# 2_NAND-eMMC.net
KiCad netlist of a schematic drawn in Altium Designer
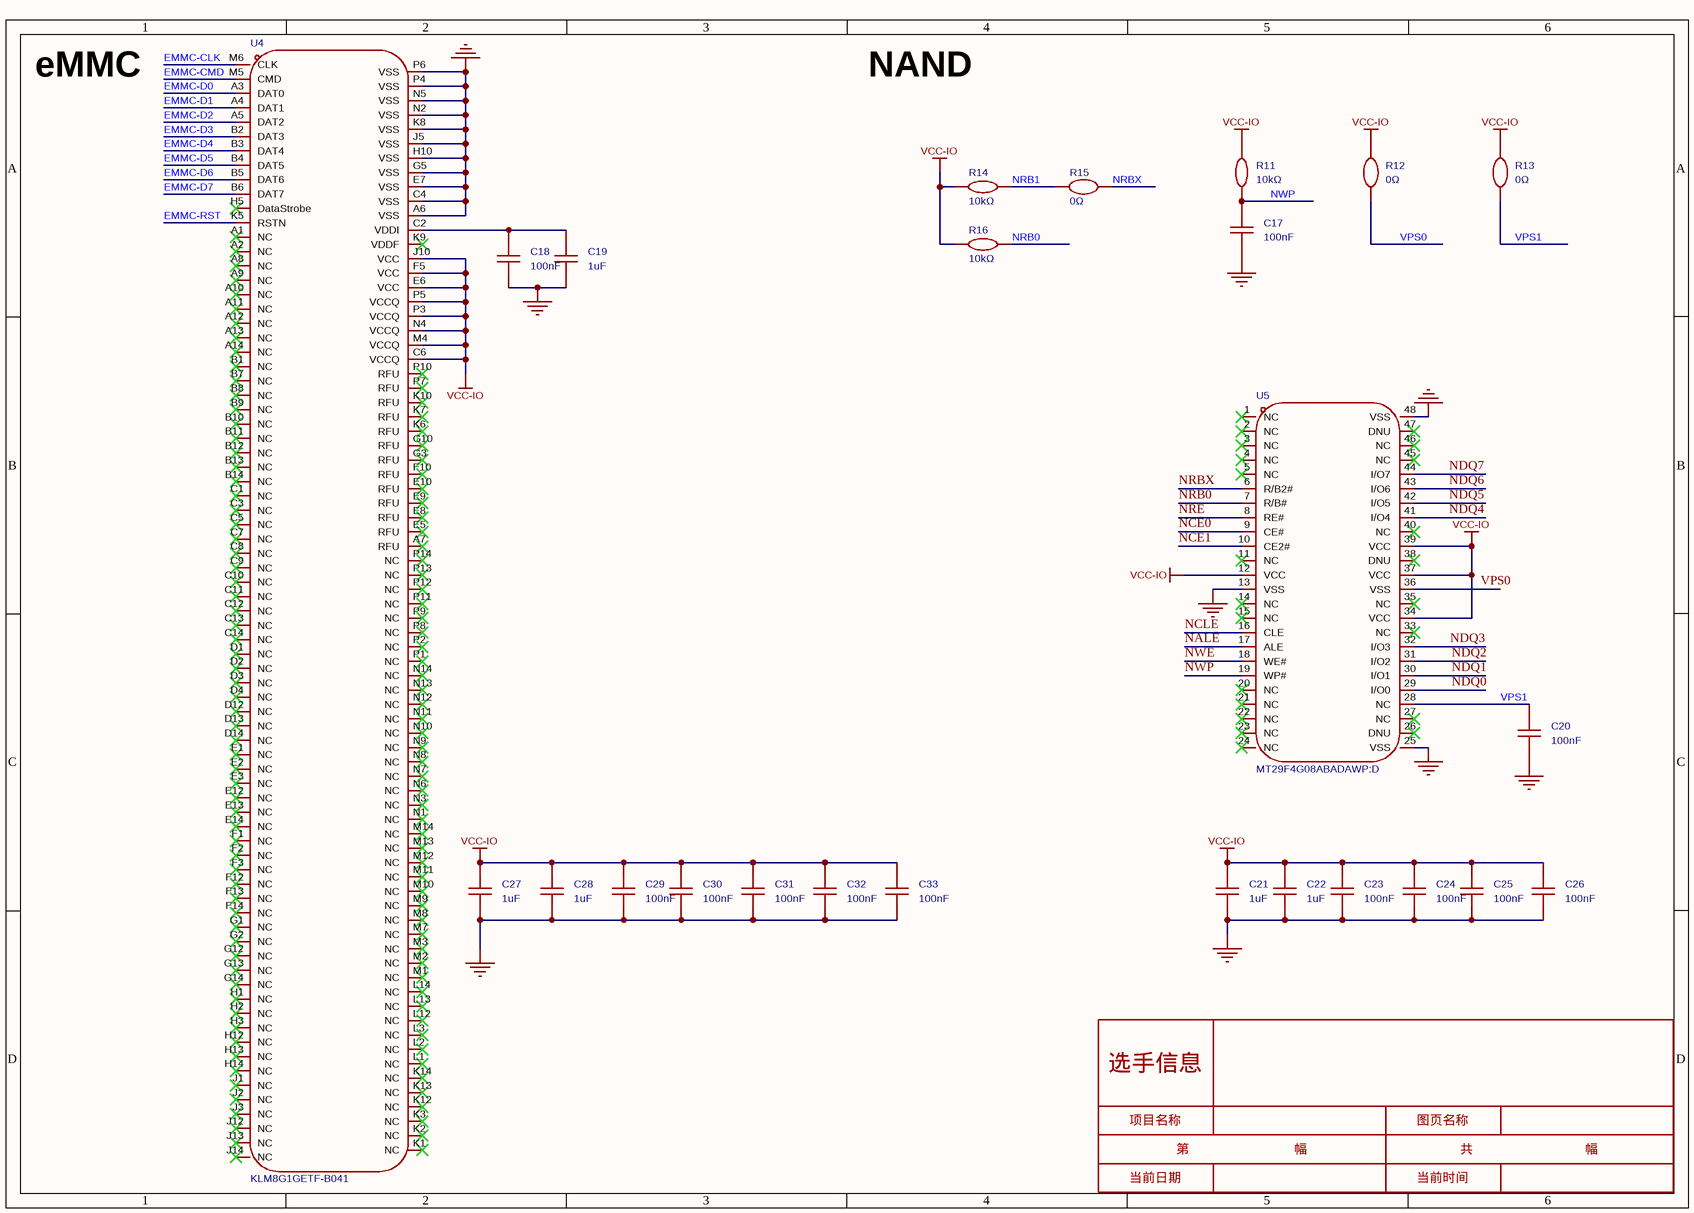
[diagram p0: 2_NAND-eMMC.schdoc]

(export (version "E")
  (design (tool "Eeschema 10.0.6"))
  (components
    (comp (ref "C17")
      (value "100nF")
      (footprint "C0402")
      (description "容值:100nF;精度:±10%;额定电压:16V;温度系数:X7R;")
      (fields (field (name "MANUFACTURER") "SAMSUNG(三星)") (field (name "MANUFACTURERPART") "CL05B104KO5NNNC"))
      (libsource (lib "altium-import") (part "root_3_CL05B104KO5NNNC_"))
    )
    (comp (ref "C18")
      (value "100nF")
      (footprint "C0402")
      (description "容值:100nF;精度:±10%;额定电压:16V;温度系数:X7R;")
      (fields (field (name "MANUFACTURER") "SAMSUNG(三星)") (field (name "MANUFACTURERPART") "CL05B104KO5NNNC"))
      (libsource (lib "altium-import") (part "root_3_CL05B104KO5NNNC_"))
    )
    (comp (ref "C19")
      (value "1uF")
      (footprint "C0402")
      (description "容值:1uF;精度:±10%;额定电压:50V;温度系数:X5R;")
      (fields (field (name "MANUFACTURER") "HRE(芯声)") (field (name "MANUFACTURERPART") "CGA0402X5R105K500GT"))
      (libsource (lib "altium-import") (part "root_3_CGA0402X5R105K500GT_"))
    )
    (comp (ref "C20")
      (value "100nF")
      (footprint "C0402")
      (description "容值:100nF;精度:±10%;额定电压:16V;温度系数:X7R;")
      (fields
        (field (name "MANUFACTURER") "SAMSUNG(三星)")
        (field (name "MANUFACTURER PART") "CL05B104KO5NNNC")
      )
      (libsource (lib "altium-import") (part "root_3_CL05B104KO5NNNC_"))
    )
    (comp (ref "C21")
      (value "1uF")
      (footprint "C0402")
      (description "容值:1uF;精度:±10%;额定电压:50V;温度系数:X5R;")
      (fields
        (field (name "MANUFACTURER") "HRE(芯声)")
        (field (name "MANUFACTURER PART") "CGA0402X5R105K500GT")
      )
      (libsource (lib "altium-import") (part "root_3_CGA0402X5R105K500GT_"))
    )
    (comp (ref "C22")
      (value "1uF")
      (footprint "C0402")
      (description "容值:1uF;精度:±10%;额定电压:50V;温度系数:X5R;")
      (fields
        (field (name "MANUFACTURER") "HRE(芯声)")
        (field (name "MANUFACTURER PART") "CGA0402X5R105K500GT")
      )
      (libsource (lib "altium-import") (part "root_3_CGA0402X5R105K500GT_"))
    )
    (comp (ref "C23")
      (value "100nF")
      (footprint "C0402")
      (description "容值:100nF;精度:±10%;额定电压:16V;温度系数:X7R;")
      (fields
        (field (name "MANUFACTURER") "SAMSUNG(三星)")
        (field (name "MANUFACTURER PART") "CL05B104KO5NNNC")
      )
      (libsource (lib "altium-import") (part "root_3_CL05B104KO5NNNC_"))
    )
    (comp (ref "C24")
      (value "100nF")
      (footprint "C0402")
      (description "容值:100nF;精度:±10%;额定电压:16V;温度系数:X7R;")
      (fields
        (field (name "MANUFACTURER") "SAMSUNG(三星)")
        (field (name "MANUFACTURER PART") "CL05B104KO5NNNC")
      )
      (libsource (lib "altium-import") (part "root_3_CL05B104KO5NNNC_"))
    )
    (comp (ref "C25")
      (value "100nF")
      (footprint "C0402")
      (description "容值:100nF;精度:±10%;额定电压:16V;温度系数:X7R;")
      (fields
        (field (name "MANUFACTURER") "SAMSUNG(三星)")
        (field (name "MANUFACTURER PART") "CL05B104KO5NNNC")
      )
      (libsource (lib "altium-import") (part "root_3_CL05B104KO5NNNC_"))
    )
    (comp (ref "C26")
      (value "100nF")
      (footprint "C0402")
      (description "容值:100nF;精度:±10%;额定电压:16V;温度系数:X7R;")
      (fields
        (field (name "MANUFACTURER") "SAMSUNG(三星)")
        (field (name "MANUFACTURER PART") "CL05B104KO5NNNC")
      )
      (libsource (lib "altium-import") (part "root_3_CL05B104KO5NNNC_"))
    )
    (comp (ref "C27")
      (value "1uF")
      (footprint "C0402")
      (description "容值:1uF;精度:±10%;额定电压:50V;温度系数:X5R;")
      (fields (field (name "MANUFACTURER") "HRE(芯声)") (field (name "MANUFACTURERPART") "CGA0402X5R105K500GT"))
      (libsource (lib "altium-import") (part "root_3_CGA0402X5R105K500GT_"))
    )
    (comp (ref "C28")
      (value "1uF")
      (footprint "C0402")
      (description "容值:1uF;精度:±10%;额定电压:50V;温度系数:X5R;")
      (fields (field (name "MANUFACTURER") "HRE(芯声)") (field (name "MANUFACTURERPART") "CGA0402X5R105K500GT"))
      (libsource (lib "altium-import") (part "root_3_CGA0402X5R105K500GT_"))
    )
    (comp (ref "C29")
      (value "100nF")
      (footprint "C0402")
      (description "容值:100nF;精度:±10%;额定电压:16V;温度系数:X7R;")
      (fields (field (name "MANUFACTURER") "SAMSUNG(三星)") (field (name "MANUFACTURERPART") "CL05B104KO5NNNC"))
      (libsource (lib "altium-import") (part "root_3_CL05B104KO5NNNC_"))
    )
    (comp (ref "C30")
      (value "100nF")
      (footprint "C0402")
      (description "容值:100nF;精度:±10%;额定电压:16V;温度系数:X7R;")
      (fields
        (field (name "MANUFACTURER") "SAMSUNG(三星)")
        (field (name "MANUFACTURER PART") "CL05B104KO5NNNC")
      )
      (libsource (lib "altium-import") (part "root_3_CL05B104KO5NNNC_"))
    )
    (comp (ref "C31")
      (value "100nF")
      (footprint "C0402")
      (description "容值:100nF;精度:±10%;额定电压:16V;温度系数:X7R;")
      (fields
        (field (name "MANUFACTURER") "SAMSUNG(三星)")
        (field (name "MANUFACTURER PART") "CL05B104KO5NNNC")
      )
      (libsource (lib "altium-import") (part "root_3_CL05B104KO5NNNC_"))
    )
    (comp (ref "C32")
      (value "100nF")
      (footprint "C0402")
      (description "容值:100nF;精度:±10%;额定电压:16V;温度系数:X7R;")
      (fields
        (field (name "MANUFACTURER") "SAMSUNG(三星)")
        (field (name "MANUFACTURER PART") "CL05B104KO5NNNC")
      )
      (libsource (lib "altium-import") (part "root_3_CL05B104KO5NNNC_"))
    )
    (comp (ref "C33")
      (value "100nF")
      (footprint "C0402")
      (description "容值:100nF;精度:±10%;额定电压:16V;温度系数:X7R;")
      (fields
        (field (name "MANUFACTURER") "SAMSUNG(三星)")
        (field (name "MANUFACTURER PART") "CL05B104KO5NNNC")
      )
      (libsource (lib "altium-import") (part "root_3_CL05B104KO5NNNC_"))
    )
    (comp (ref "R11")
      (value "10kΩ")
      (footprint "R0402")
      (description "电阻类型:厚膜电阻;阻值:10kΩ;精度:±1%;功率:62.5mW;工作电压:50V;温度系数:±100ppm/℃;")
      (fields (field (name "MANUFACTURER") "YAGEO(国巨)") (field (name "MANUFACTURERPART") "RC0402FR-0710KL"))
      (libsource (lib "altium-import") (part "root_1_RC0402FR-0710KL_"))
    )
    (comp (ref "R12")
      (value "0Ω")
      (footprint "R0402")
      (description "电阻类型:厚膜电阻;阻值:0Ω;精度:±5%;功率:62.5mW;工作电压:50V;")
      (fields (field (name "MANUFACTURER") "FOJAN(富捷)") (field (name "MANUFACTURERPART") "FRC0402P000 TS"))
      (libsource (lib "altium-import") (part "root_1_FRC0402P000 TS_"))
    )
    (comp (ref "R13")
      (value "0Ω")
      (footprint "R0402")
      (description "电阻类型:厚膜电阻;阻值:0Ω;精度:±5%;功率:62.5mW;工作电压:50V;")
      (fields (field (name "MANUFACTURER") "FOJAN(富捷)") (field (name "MANUFACTURERPART") "FRC0402P000 TS"))
      (libsource (lib "altium-import") (part "root_1_FRC0402P000 TS_"))
    )
    (comp (ref "R14")
      (value "10kΩ")
      (footprint "R0402")
      (description "电阻类型:厚膜电阻;阻值:10kΩ;精度:±1%;功率:62.5mW;工作电压:50V;温度系数:±100ppm/℃;")
      (fields (field (name "MANUFACTURER") "YAGEO(国巨)") (field (name "MANUFACTURERPART") "RC0402FR-0710KL"))
      (libsource (lib "altium-import") (part "root_2_RC0402FR-0710KL_"))
    )
    (comp (ref "R15")
      (value "0Ω")
      (footprint "R0402")
      (description "电阻类型:厚膜电阻;阻值:0Ω;精度:±5%;功率:62.5mW;工作电压:50V;")
      (fields (field (name "MANUFACTURER") "FOJAN(富捷)") (field (name "MANUFACTURERPART") "FRC0402P000 TS"))
      (libsource (lib "altium-import") (part "root_2_FRC0402P000 TS_"))
    )
    (comp (ref "R16")
      (value "10kΩ")
      (footprint "R0402")
      (description "电阻类型:厚膜电阻;阻值:10kΩ;精度:±1%;功率:62.5mW;工作电压:50V;温度系数:±100ppm/℃;")
      (fields (field (name "MANUFACTURER") "YAGEO(国巨)") (field (name "MANUFACTURERPART") "RC0402FR-0710KL"))
      (libsource (lib "altium-import") (part "root_2_RC0402FR-0710KL_"))
    )
    (comp (ref "U4")
      (value "KLM8G1GETF-B041")
      (footprint "FBGA-153_L13.0-W11.5-P0.50_KLMAG1JETD-B041")
      (description "配置:-;接口类型:eMMC 5.1;存储容量:8GB;")
      (fields (field (name "MANUFACTURER") "SAMSUNG(三星半导体)"))
      (libsource (lib "altium-import") (part "root_0_KLM8G1GETF-B041_"))
    )
    (comp (ref "U5")
      (value "MT29F4G08ABADAWP:D")
      (footprint "TSOP-48_L18.5-W12.2-P0.50-LS20.0-TL")
      (description "存储容量:4Gbit;时钟频率(fc):-;工作电压:2.7V~3.6V;")
      (fields (field (name "MANUFACTURER") "micron(镁光)"))
      (libsource (lib "altium-import") (part "root_0_MT29F4G08ABADAWP{colon}D_"))
    )
  )
  (nets
    (net (code "2") (name "/EMMC-CLK") (class "Default")
      (node (ref "U4") (pin "M6") (pinfunction "CLK_M6") (pintype "passive"))
    )
    (net (code "3") (name "/EMMC-CMD") (class "Default")
      (node (ref "U4") (pin "M5") (pinfunction "CMD_M5") (pintype "passive"))
    )
    (net (code "4") (name "/EMMC-D0") (class "Default")
      (node (ref "U4") (pin "A3") (pinfunction "DAT0_A3") (pintype "passive"))
    )
    (net (code "5") (name "/EMMC-D1") (class "Default")
      (node (ref "U4") (pin "A4") (pinfunction "DAT1_A4") (pintype "passive"))
    )
    (net (code "6") (name "/EMMC-D2") (class "Default")
      (node (ref "U4") (pin "A5") (pinfunction "DAT2_A5") (pintype "passive"))
    )
    (net (code "7") (name "/EMMC-D3") (class "Default")
      (node (ref "U4") (pin "B2") (pinfunction "DAT3_B2") (pintype "passive"))
    )
    (net (code "8") (name "/EMMC-D4") (class "Default")
      (node (ref "U4") (pin "B3") (pinfunction "DAT4_B3") (pintype "passive"))
    )
    (net (code "9") (name "/EMMC-D5") (class "Default")
      (node (ref "U4") (pin "B4") (pinfunction "DAT5_B4") (pintype "passive"))
    )
    (net (code "10") (name "/EMMC-D6") (class "Default")
      (node (ref "U4") (pin "B5") (pinfunction "DAT6_B5") (pintype "passive"))
    )
    (net (code "11") (name "/EMMC-D7") (class "Default")
      (node (ref "U4") (pin "B6") (pinfunction "DAT7_B6") (pintype "passive"))
    )
    (net (code "12") (name "/EMMC-RST") (class "Default")
      (node (ref "U4") (pin "K5") (pinfunction "RSTN_K5") (pintype "passive"))
    )
    (net (code "13") (name "/NALE") (class "Default")
      (node (ref "U5") (pin "17") (pinfunction "ALE_17") (pintype "passive"))
    )
    (net (code "14") (name "/NCE0") (class "Default")
      (node (ref "U5") (pin "9") (pinfunction "CE#_9") (pintype "passive"))
    )
    (net (code "15") (name "/NCE1") (class "Default")
      (node (ref "U5") (pin "10") (pinfunction "CE2#_10") (pintype "passive"))
    )
    (net (code "16") (name "/NCLE") (class "Default")
      (node (ref "U5") (pin "16") (pinfunction "CLE_16") (pintype "passive"))
    )
    (net (code "17") (name "/NDQ0") (class "Default")
      (node (ref "U5") (pin "29") (pinfunction "I/O0_29") (pintype "passive"))
    )
    (net (code "18") (name "/NDQ1") (class "Default")
      (node (ref "U5") (pin "30") (pinfunction "I/O1_30") (pintype "passive"))
    )
    (net (code "19") (name "/NDQ2") (class "Default")
      (node (ref "U5") (pin "31") (pinfunction "I/O2_31") (pintype "passive"))
    )
    (net (code "20") (name "/NDQ3") (class "Default")
      (node (ref "U5") (pin "32") (pinfunction "I/O3_32") (pintype "passive"))
    )
    (net (code "21") (name "/NDQ4") (class "Default")
      (node (ref "U5") (pin "41") (pinfunction "I/O4_41") (pintype "passive"))
    )
    (net (code "22") (name "/NDQ5") (class "Default")
      (node (ref "U5") (pin "42") (pinfunction "I/O5_42") (pintype "passive"))
    )
    (net (code "23") (name "/NDQ6") (class "Default")
      (node (ref "U5") (pin "43") (pinfunction "I/O6_43") (pintype "passive"))
    )
    (net (code "24") (name "/NDQ7") (class "Default")
      (node (ref "U5") (pin "44") (pinfunction "I/O7_44") (pintype "passive"))
    )
    (net (code "25") (name "/NRB0") (class "Default")
      (node (ref "R16") (pin "1") (pinfunction "1_1") (pintype "passive"))
      (node (ref "U5") (pin "7") (pinfunction "R/B#_7") (pintype "passive"))
    )
    (net (code "26") (name "/NRB1") (class "Default")
      (node (ref "R14") (pin "1") (pinfunction "1_1") (pintype "passive"))
      (node (ref "R15") (pin "2") (pinfunction "2_2") (pintype "passive"))
    )
    (net (code "27") (name "/NRBX") (class "Default")
      (node (ref "R15") (pin "1") (pinfunction "1_1") (pintype "passive"))
      (node (ref "U5") (pin "6") (pinfunction "R/B2#_6") (pintype "passive"))
    )
    (net (code "28") (name "/NRE") (class "Default")
      (node (ref "U5") (pin "8") (pinfunction "RE#_8") (pintype "passive"))
    )
    (net (code "29") (name "/NWE") (class "Default")
      (node (ref "U5") (pin "18") (pinfunction "WE#_18") (pintype "passive"))
    )
    (net (code "30") (name "/NWP") (class "Default")
      (node (ref "C17") (pin "1") (pinfunction "1_1") (pintype "passive"))
      (node (ref "R11") (pin "1") (pinfunction "1_1") (pintype "passive"))
      (node (ref "U5") (pin "19") (pinfunction "WP#_19") (pintype "passive"))
    )
    (net (code "31") (name "/VPS0") (class "Default")
      (node (ref "R12") (pin "1") (pinfunction "1_1") (pintype "passive"))
      (node (ref "U5") (pin "36") (pinfunction "VSS_36") (pintype "passive"))
    )
    (net (code "32") (name "/VPS1") (class "Default")
      (node (ref "C20") (pin "1") (pinfunction "1_1") (pintype "passive"))
      (node (ref "R13") (pin "1") (pinfunction "1_1") (pintype "passive"))
      (node (ref "U5") (pin "28") (pinfunction "NC_28") (pintype "passive"))
    )
    (net (code "33") (name "GND") (class "Default")
      (node (ref "C17") (pin "2") (pinfunction "2_2") (pintype "passive"))
      (node (ref "C18") (pin "2") (pinfunction "2_2") (pintype "passive"))
      (node (ref "C19") (pin "2") (pinfunction "2_2") (pintype "passive"))
      (node (ref "C20") (pin "2") (pinfunction "2_2") (pintype "passive"))
      (node (ref "C21") (pin "2") (pinfunction "2_2") (pintype "passive"))
      (node (ref "C22") (pin "2") (pinfunction "2_2") (pintype "passive"))
      (node (ref "C23") (pin "2") (pinfunction "2_2") (pintype "passive"))
      (node (ref "C24") (pin "2") (pinfunction "2_2") (pintype "passive"))
      (node (ref "C25") (pin "2") (pinfunction "2_2") (pintype "passive"))
      (node (ref "C26") (pin "2") (pinfunction "2_2") (pintype "passive"))
      (node (ref "C27") (pin "2") (pinfunction "2_2") (pintype "passive"))
      (node (ref "C28") (pin "2") (pinfunction "2_2") (pintype "passive"))
      (node (ref "C29") (pin "2") (pinfunction "2_2") (pintype "passive"))
      (node (ref "C30") (pin "2") (pinfunction "2_2") (pintype "passive"))
      (node (ref "C31") (pin "2") (pinfunction "2_2") (pintype "passive"))
      (node (ref "C32") (pin "2") (pinfunction "2_2") (pintype "passive"))
      (node (ref "C33") (pin "2") (pinfunction "2_2") (pintype "passive"))
      (node (ref "U4") (pin "A6") (pinfunction "VSS_A6") (pintype "passive"))
      (node (ref "U4") (pin "C4") (pinfunction "VSS_C4") (pintype "passive"))
      (node (ref "U4") (pin "E7") (pinfunction "VSS_E7") (pintype "passive"))
      (node (ref "U4") (pin "G5") (pinfunction "VSS_G5") (pintype "passive"))
      (node (ref "U4") (pin "H10") (pinfunction "VSS_H10") (pintype "passive"))
      (node (ref "U4") (pin "J5") (pinfunction "VSS_J5") (pintype "passive"))
      (node (ref "U4") (pin "K8") (pinfunction "VSS_K8") (pintype "passive"))
      (node (ref "U4") (pin "N2") (pinfunction "VSS_N2") (pintype "passive"))
      (node (ref "U4") (pin "N5") (pinfunction "VSS_N5") (pintype "passive"))
      (node (ref "U4") (pin "P4") (pinfunction "VSS_P4") (pintype "passive"))
      (node (ref "U4") (pin "P6") (pinfunction "VSS_P6") (pintype "passive"))
      (node (ref "U5") (pin "13") (pinfunction "VSS_13") (pintype "passive"))
      (node (ref "U5") (pin "25") (pinfunction "VSS_25") (pintype "passive"))
      (node (ref "U5") (pin "48") (pinfunction "VSS_48") (pintype "passive"))
    )
    (net (code "34") (name "Net-(U4-VDDI)") (class "Default")
      (node (ref "C18") (pin "1") (pinfunction "1_1") (pintype "passive"))
      (node (ref "C19") (pin "1") (pinfunction "1_1") (pintype "passive"))
      (node (ref "U4") (pin "C2") (pinfunction "VDDI_C2") (pintype "passive"))
    )
    (net (code "35") (name "VCC-IO") (class "Default")
      (node (ref "C21") (pin "1") (pinfunction "1_1") (pintype "passive"))
      (node (ref "C22") (pin "1") (pinfunction "1_1") (pintype "passive"))
      (node (ref "C23") (pin "1") (pinfunction "1_1") (pintype "passive"))
      (node (ref "C24") (pin "1") (pinfunction "1_1") (pintype "passive"))
      (node (ref "C25") (pin "1") (pinfunction "1_1") (pintype "passive"))
      (node (ref "C26") (pin "1") (pinfunction "1_1") (pintype "passive"))
      (node (ref "C27") (pin "1") (pinfunction "1_1") (pintype "passive"))
      (node (ref "C28") (pin "1") (pinfunction "1_1") (pintype "passive"))
      (node (ref "C29") (pin "1") (pinfunction "1_1") (pintype "passive"))
      (node (ref "C30") (pin "1") (pinfunction "1_1") (pintype "passive"))
      (node (ref "C31") (pin "1") (pinfunction "1_1") (pintype "passive"))
      (node (ref "C32") (pin "1") (pinfunction "1_1") (pintype "passive"))
      (node (ref "C33") (pin "1") (pinfunction "1_1") (pintype "passive"))
      (node (ref "R11") (pin "2") (pinfunction "2_2") (pintype "passive"))
      (node (ref "R12") (pin "2") (pinfunction "2_2") (pintype "passive"))
      (node (ref "R13") (pin "2") (pinfunction "2_2") (pintype "passive"))
      (node (ref "R14") (pin "2") (pinfunction "2_2") (pintype "passive"))
      (node (ref "R16") (pin "2") (pinfunction "2_2") (pintype "passive"))
      (node (ref "U4") (pin "C6") (pinfunction "VCCQ_C6") (pintype "passive"))
      (node (ref "U4") (pin "E6") (pinfunction "VCC_E6") (pintype "passive"))
      (node (ref "U4") (pin "F5") (pinfunction "VCC_F5") (pintype "passive"))
      (node (ref "U4") (pin "J10") (pinfunction "VCC_J10") (pintype "passive"))
      (node (ref "U4") (pin "M4") (pinfunction "VCCQ_M4") (pintype "passive"))
      (node (ref "U4") (pin "N4") (pinfunction "VCCQ_N4") (pintype "passive"))
      (node (ref "U4") (pin "P3") (pinfunction "VCCQ_P3") (pintype "passive"))
      (node (ref "U4") (pin "P5") (pinfunction "VCCQ_P5") (pintype "passive"))
      (node (ref "U5") (pin "12") (pinfunction "VCC_12") (pintype "passive"))
      (node (ref "U5") (pin "34") (pinfunction "VCC_34") (pintype "passive"))
      (node (ref "U5") (pin "37") (pinfunction "VCC_37") (pintype "passive"))
      (node (ref "U5") (pin "39") (pinfunction "VCC_39") (pintype "passive"))
    )
    (net (code "36") (name "unconnected-(U4-DataStrobe-PadH5)") (class "Default")
      (node (ref "U4") (pin "H5") (pinfunction "DataStrobe_H5") (pintype "passive+no_connect"))
    )
    (net (code "37") (name "unconnected-(U4-NC-PadA1)") (class "Default")
      (node (ref "U4") (pin "A1") (pinfunction "NC_A1") (pintype "passive+no_connect"))
    )
    (net (code "38") (name "unconnected-(U4-NC-PadA2)") (class "Default")
      (node (ref "U4") (pin "A2") (pinfunction "NC_A2") (pintype "passive+no_connect"))
    )
    (net (code "39") (name "unconnected-(U4-NC-PadA8)") (class "Default")
      (node (ref "U4") (pin "A8") (pinfunction "NC_A8") (pintype "passive+no_connect"))
    )
    (net (code "40") (name "unconnected-(U4-NC-PadA9)") (class "Default")
      (node (ref "U4") (pin "A9") (pinfunction "NC_A9") (pintype "passive+no_connect"))
    )
    (net (code "41") (name "unconnected-(U4-NC-PadA10)") (class "Default")
      (node (ref "U4") (pin "A10") (pinfunction "NC_A10") (pintype "passive+no_connect"))
    )
    (net (code "42") (name "unconnected-(U4-NC-PadA11)") (class "Default")
      (node (ref "U4") (pin "A11") (pinfunction "NC_A11") (pintype "passive+no_connect"))
    )
    (net (code "43") (name "unconnected-(U4-NC-PadA12)") (class "Default")
      (node (ref "U4") (pin "A12") (pinfunction "NC_A12") (pintype "passive+no_connect"))
    )
    (net (code "44") (name "unconnected-(U4-NC-PadA13)") (class "Default")
      (node (ref "U4") (pin "A13") (pinfunction "NC_A13") (pintype "passive+no_connect"))
    )
    (net (code "45") (name "unconnected-(U4-NC-PadA14)") (class "Default")
      (node (ref "U4") (pin "A14") (pinfunction "NC_A14") (pintype "passive+no_connect"))
    )
    (net (code "46") (name "unconnected-(U4-NC-PadB1)") (class "Default")
      (node (ref "U4") (pin "B1") (pinfunction "NC_B1") (pintype "passive+no_connect"))
    )
    (net (code "47") (name "unconnected-(U4-NC-PadB7)") (class "Default")
      (node (ref "U4") (pin "B7") (pinfunction "NC_B7") (pintype "passive+no_connect"))
    )
    (net (code "48") (name "unconnected-(U4-NC-PadB8)") (class "Default")
      (node (ref "U4") (pin "B8") (pinfunction "NC_B8") (pintype "passive+no_connect"))
    )
    (net (code "49") (name "unconnected-(U4-NC-PadB9)") (class "Default")
      (node (ref "U4") (pin "B9") (pinfunction "NC_B9") (pintype "passive+no_connect"))
    )
    (net (code "50") (name "unconnected-(U4-NC-PadB10)") (class "Default")
      (node (ref "U4") (pin "B10") (pinfunction "NC_B10") (pintype "passive+no_connect"))
    )
    (net (code "51") (name "unconnected-(U4-NC-PadB11)") (class "Default")
      (node (ref "U4") (pin "B11") (pinfunction "NC_B11") (pintype "passive+no_connect"))
    )
    (net (code "52") (name "unconnected-(U4-NC-PadB12)") (class "Default")
      (node (ref "U4") (pin "B12") (pinfunction "NC_B12") (pintype "passive+no_connect"))
    )
    (net (code "53") (name "unconnected-(U4-NC-PadB13)") (class "Default")
      (node (ref "U4") (pin "B13") (pinfunction "NC_B13") (pintype "passive+no_connect"))
    )
    (net (code "54") (name "unconnected-(U4-NC-PadB14)") (class "Default")
      (node (ref "U4") (pin "B14") (pinfunction "NC_B14") (pintype "passive+no_connect"))
    )
    (net (code "55") (name "unconnected-(U4-NC-PadC1)") (class "Default")
      (node (ref "U4") (pin "C1") (pinfunction "NC_C1") (pintype "passive+no_connect"))
    )
    (net (code "56") (name "unconnected-(U4-NC-PadC3)") (class "Default")
      (node (ref "U4") (pin "C3") (pinfunction "NC_C3") (pintype "passive+no_connect"))
    )
    (net (code "57") (name "unconnected-(U4-NC-PadC5)") (class "Default")
      (node (ref "U4") (pin "C5") (pinfunction "NC_C5") (pintype "passive+no_connect"))
    )
    (net (code "58") (name "unconnected-(U4-NC-PadC7)") (class "Default")
      (node (ref "U4") (pin "C7") (pinfunction "NC_C7") (pintype "passive+no_connect"))
    )
    (net (code "59") (name "unconnected-(U4-NC-PadC8)") (class "Default")
      (node (ref "U4") (pin "C8") (pinfunction "NC_C8") (pintype "passive+no_connect"))
    )
    (net (code "60") (name "unconnected-(U4-NC-PadC9)") (class "Default")
      (node (ref "U4") (pin "C9") (pinfunction "NC_C9") (pintype "passive+no_connect"))
    )
    (net (code "61") (name "unconnected-(U4-NC-PadC10)") (class "Default")
      (node (ref "U4") (pin "C10") (pinfunction "NC_C10") (pintype "passive+no_connect"))
    )
    (net (code "62") (name "unconnected-(U4-NC-PadC11)") (class "Default")
      (node (ref "U4") (pin "C11") (pinfunction "NC_C11") (pintype "passive+no_connect"))
    )
    (net (code "63") (name "unconnected-(U4-NC-PadC12)") (class "Default")
      (node (ref "U4") (pin "C12") (pinfunction "NC_C12") (pintype "passive+no_connect"))
    )
    (net (code "64") (name "unconnected-(U4-NC-PadC13)") (class "Default")
      (node (ref "U4") (pin "C13") (pinfunction "NC_C13") (pintype "passive+no_connect"))
    )
    (net (code "65") (name "unconnected-(U4-NC-PadC14)") (class "Default")
      (node (ref "U4") (pin "C14") (pinfunction "NC_C14") (pintype "passive+no_connect"))
    )
    (net (code "66") (name "unconnected-(U4-NC-PadD1)") (class "Default")
      (node (ref "U4") (pin "D1") (pinfunction "NC_D1") (pintype "passive+no_connect"))
    )
    (net (code "67") (name "unconnected-(U4-NC-PadD2)") (class "Default")
      (node (ref "U4") (pin "D2") (pinfunction "NC_D2") (pintype "passive+no_connect"))
    )
    (net (code "68") (name "unconnected-(U4-NC-PadD3)") (class "Default")
      (node (ref "U4") (pin "D3") (pinfunction "NC_D3") (pintype "passive+no_connect"))
    )
    (net (code "69") (name "unconnected-(U4-NC-PadD4)") (class "Default")
      (node (ref "U4") (pin "D4") (pinfunction "NC_D4") (pintype "passive+no_connect"))
    )
    (net (code "70") (name "unconnected-(U4-NC-PadD12)") (class "Default")
      (node (ref "U4") (pin "D12") (pinfunction "NC_D12") (pintype "passive+no_connect"))
    )
    (net (code "71") (name "unconnected-(U4-NC-PadD13)") (class "Default")
      (node (ref "U4") (pin "D13") (pinfunction "NC_D13") (pintype "passive+no_connect"))
    )
    (net (code "72") (name "unconnected-(U4-NC-PadD14)") (class "Default")
      (node (ref "U4") (pin "D14") (pinfunction "NC_D14") (pintype "passive+no_connect"))
    )
    (net (code "73") (name "unconnected-(U4-NC-PadE1)") (class "Default")
      (node (ref "U4") (pin "E1") (pinfunction "NC_E1") (pintype "passive+no_connect"))
    )
    (net (code "74") (name "unconnected-(U4-NC-PadE2)") (class "Default")
      (node (ref "U4") (pin "E2") (pinfunction "NC_E2") (pintype "passive+no_connect"))
    )
    (net (code "75") (name "unconnected-(U4-NC-PadE3)") (class "Default")
      (node (ref "U4") (pin "E3") (pinfunction "NC_E3") (pintype "passive+no_connect"))
    )
    (net (code "76") (name "unconnected-(U4-NC-PadE12)") (class "Default")
      (node (ref "U4") (pin "E12") (pinfunction "NC_E12") (pintype "passive+no_connect"))
    )
    (net (code "77") (name "unconnected-(U4-NC-PadE13)") (class "Default")
      (node (ref "U4") (pin "E13") (pinfunction "NC_E13") (pintype "passive+no_connect"))
    )
    (net (code "78") (name "unconnected-(U4-NC-PadE14)") (class "Default")
      (node (ref "U4") (pin "E14") (pinfunction "NC_E14") (pintype "passive+no_connect"))
    )
    (net (code "79") (name "unconnected-(U4-NC-PadF1)") (class "Default")
      (node (ref "U4") (pin "F1") (pinfunction "NC_F1") (pintype "passive+no_connect"))
    )
    (net (code "80") (name "unconnected-(U4-NC-PadF2)") (class "Default")
      (node (ref "U4") (pin "F2") (pinfunction "NC_F2") (pintype "passive+no_connect"))
    )
    (net (code "81") (name "unconnected-(U4-NC-PadF3)") (class "Default")
      (node (ref "U4") (pin "F3") (pinfunction "NC_F3") (pintype "passive+no_connect"))
    )
    (net (code "82") (name "unconnected-(U4-NC-PadF12)") (class "Default")
      (node (ref "U4") (pin "F12") (pinfunction "NC_F12") (pintype "passive+no_connect"))
    )
    (net (code "83") (name "unconnected-(U4-NC-PadF13)") (class "Default")
      (node (ref "U4") (pin "F13") (pinfunction "NC_F13") (pintype "passive+no_connect"))
    )
    (net (code "84") (name "unconnected-(U4-NC-PadF14)") (class "Default")
      (node (ref "U4") (pin "F14") (pinfunction "NC_F14") (pintype "passive+no_connect"))
    )
    (net (code "85") (name "unconnected-(U4-NC-PadG1)") (class "Default")
      (node (ref "U4") (pin "G1") (pinfunction "NC_G1") (pintype "passive+no_connect"))
    )
    (net (code "86") (name "unconnected-(U4-NC-PadG2)") (class "Default")
      (node (ref "U4") (pin "G2") (pinfunction "NC_G2") (pintype "passive+no_connect"))
    )
    (net (code "87") (name "unconnected-(U4-NC-PadG12)") (class "Default")
      (node (ref "U4") (pin "G12") (pinfunction "NC_G12") (pintype "passive+no_connect"))
    )
    (net (code "88") (name "unconnected-(U4-NC-PadG13)") (class "Default")
      (node (ref "U4") (pin "G13") (pinfunction "NC_G13") (pintype "passive+no_connect"))
    )
    (net (code "89") (name "unconnected-(U4-NC-PadG14)") (class "Default")
      (node (ref "U4") (pin "G14") (pinfunction "NC_G14") (pintype "passive+no_connect"))
    )
    (net (code "90") (name "unconnected-(U4-NC-PadH1)") (class "Default")
      (node (ref "U4") (pin "H1") (pinfunction "NC_H1") (pintype "passive+no_connect"))
    )
    (net (code "91") (name "unconnected-(U4-NC-PadH2)") (class "Default")
      (node (ref "U4") (pin "H2") (pinfunction "NC_H2") (pintype "passive+no_connect"))
    )
    (net (code "92") (name "unconnected-(U4-NC-PadH3)") (class "Default")
      (node (ref "U4") (pin "H3") (pinfunction "NC_H3") (pintype "passive+no_connect"))
    )
    (net (code "93") (name "unconnected-(U4-NC-PadH12)") (class "Default")
      (node (ref "U4") (pin "H12") (pinfunction "NC_H12") (pintype "passive+no_connect"))
    )
    (net (code "94") (name "unconnected-(U4-NC-PadH13)") (class "Default")
      (node (ref "U4") (pin "H13") (pinfunction "NC_H13") (pintype "passive+no_connect"))
    )
    (net (code "95") (name "unconnected-(U4-NC-PadH14)") (class "Default")
      (node (ref "U4") (pin "H14") (pinfunction "NC_H14") (pintype "passive+no_connect"))
    )
    (net (code "96") (name "unconnected-(U4-NC-PadJ1)") (class "Default")
      (node (ref "U4") (pin "J1") (pinfunction "NC_J1") (pintype "passive+no_connect"))
    )
    (net (code "97") (name "unconnected-(U4-NC-PadJ2)") (class "Default")
      (node (ref "U4") (pin "J2") (pinfunction "NC_J2") (pintype "passive+no_connect"))
    )
    (net (code "98") (name "unconnected-(U4-NC-PadJ3)") (class "Default")
      (node (ref "U4") (pin "J3") (pinfunction "NC_J3") (pintype "passive+no_connect"))
    )
    (net (code "99") (name "unconnected-(U4-NC-PadJ12)") (class "Default")
      (node (ref "U4") (pin "J12") (pinfunction "NC_J12") (pintype "passive+no_connect"))
    )
    (net (code "100") (name "unconnected-(U4-NC-PadJ13)") (class "Default")
      (node (ref "U4") (pin "J13") (pinfunction "NC_J13") (pintype "passive+no_connect"))
    )
    (net (code "101") (name "unconnected-(U4-NC-PadJ14)") (class "Default")
      (node (ref "U4") (pin "J14") (pinfunction "NC_J14") (pintype "passive+no_connect"))
    )
    (net (code "102") (name "unconnected-(U4-NC-PadK1)") (class "Default")
      (node (ref "U4") (pin "K1") (pinfunction "NC_K1") (pintype "passive+no_connect"))
    )
    (net (code "103") (name "unconnected-(U4-NC-PadK2)") (class "Default")
      (node (ref "U4") (pin "K2") (pinfunction "NC_K2") (pintype "passive+no_connect"))
    )
    (net (code "104") (name "unconnected-(U4-NC-PadK3)") (class "Default")
      (node (ref "U4") (pin "K3") (pinfunction "NC_K3") (pintype "passive+no_connect"))
    )
    (net (code "105") (name "unconnected-(U4-NC-PadK12)") (class "Default")
      (node (ref "U4") (pin "K12") (pinfunction "NC_K12") (pintype "passive+no_connect"))
    )
    (net (code "106") (name "unconnected-(U4-NC-PadK13)") (class "Default")
      (node (ref "U4") (pin "K13") (pinfunction "NC_K13") (pintype "passive+no_connect"))
    )
    (net (code "107") (name "unconnected-(U4-NC-PadK14)") (class "Default")
      (node (ref "U4") (pin "K14") (pinfunction "NC_K14") (pintype "passive+no_connect"))
    )
    (net (code "108") (name "unconnected-(U4-NC-PadL1)") (class "Default")
      (node (ref "U4") (pin "L1") (pinfunction "NC_L1") (pintype "passive+no_connect"))
    )
    (net (code "109") (name "unconnected-(U4-NC-PadL2)") (class "Default")
      (node (ref "U4") (pin "L2") (pinfunction "NC_L2") (pintype "passive+no_connect"))
    )
    (net (code "110") (name "unconnected-(U4-NC-PadL3)") (class "Default")
      (node (ref "U4") (pin "L3") (pinfunction "NC_L3") (pintype "passive+no_connect"))
    )
    (net (code "111") (name "unconnected-(U4-NC-PadL12)") (class "Default")
      (node (ref "U4") (pin "L12") (pinfunction "NC_L12") (pintype "passive+no_connect"))
    )
    (net (code "112") (name "unconnected-(U4-NC-PadL13)") (class "Default")
      (node (ref "U4") (pin "L13") (pinfunction "NC_L13") (pintype "passive+no_connect"))
    )
    (net (code "113") (name "unconnected-(U4-NC-PadL14)") (class "Default")
      (node (ref "U4") (pin "L14") (pinfunction "NC_L14") (pintype "passive+no_connect"))
    )
    (net (code "114") (name "unconnected-(U4-NC-PadM1)") (class "Default")
      (node (ref "U4") (pin "M1") (pinfunction "NC_M1") (pintype "passive+no_connect"))
    )
    (net (code "115") (name "unconnected-(U4-NC-PadM2)") (class "Default")
      (node (ref "U4") (pin "M2") (pinfunction "NC_M2") (pintype "passive+no_connect"))
    )
    (net (code "116") (name "unconnected-(U4-NC-PadM3)") (class "Default")
      (node (ref "U4") (pin "M3") (pinfunction "NC_M3") (pintype "passive+no_connect"))
    )
    (net (code "117") (name "unconnected-(U4-NC-PadM7)") (class "Default")
      (node (ref "U4") (pin "M7") (pinfunction "NC_M7") (pintype "passive+no_connect"))
    )
    (net (code "118") (name "unconnected-(U4-NC-PadM8)") (class "Default")
      (node (ref "U4") (pin "M8") (pinfunction "NC_M8") (pintype "passive+no_connect"))
    )
    (net (code "119") (name "unconnected-(U4-NC-PadM9)") (class "Default")
      (node (ref "U4") (pin "M9") (pinfunction "NC_M9") (pintype "passive+no_connect"))
    )
    (net (code "120") (name "unconnected-(U4-NC-PadM10)") (class "Default")
      (node (ref "U4") (pin "M10") (pinfunction "NC_M10") (pintype "passive+no_connect"))
    )
    (net (code "121") (name "unconnected-(U4-NC-PadM11)") (class "Default")
      (node (ref "U4") (pin "M11") (pinfunction "NC_M11") (pintype "passive+no_connect"))
    )
    (net (code "122") (name "unconnected-(U4-NC-PadM12)") (class "Default")
      (node (ref "U4") (pin "M12") (pinfunction "NC_M12") (pintype "passive+no_connect"))
    )
    (net (code "123") (name "unconnected-(U4-NC-PadM13)") (class "Default")
      (node (ref "U4") (pin "M13") (pinfunction "NC_M13") (pintype "passive+no_connect"))
    )
    (net (code "124") (name "unconnected-(U4-NC-PadM14)") (class "Default")
      (node (ref "U4") (pin "M14") (pinfunction "NC_M14") (pintype "passive+no_connect"))
    )
    (net (code "125") (name "unconnected-(U4-NC-PadN1)") (class "Default")
      (node (ref "U4") (pin "N1") (pinfunction "NC_N1") (pintype "passive+no_connect"))
    )
    (net (code "126") (name "unconnected-(U4-NC-PadN3)") (class "Default")
      (node (ref "U4") (pin "N3") (pinfunction "NC_N3") (pintype "passive+no_connect"))
    )
    (net (code "127") (name "unconnected-(U4-NC-PadN6)") (class "Default")
      (node (ref "U4") (pin "N6") (pinfunction "NC_N6") (pintype "passive+no_connect"))
    )
    (net (code "128") (name "unconnected-(U4-NC-PadN7)") (class "Default")
      (node (ref "U4") (pin "N7") (pinfunction "NC_N7") (pintype "passive+no_connect"))
    )
    (net (code "129") (name "unconnected-(U4-NC-PadN8)") (class "Default")
      (node (ref "U4") (pin "N8") (pinfunction "NC_N8") (pintype "passive+no_connect"))
    )
    (net (code "130") (name "unconnected-(U4-NC-PadN9)") (class "Default")
      (node (ref "U4") (pin "N9") (pinfunction "NC_N9") (pintype "passive+no_connect"))
    )
    (net (code "131") (name "unconnected-(U4-NC-PadN10)") (class "Default")
      (node (ref "U4") (pin "N10") (pinfunction "NC_N10") (pintype "passive+no_connect"))
    )
    (net (code "132") (name "unconnected-(U4-NC-PadN11)") (class "Default")
      (node (ref "U4") (pin "N11") (pinfunction "NC_N11") (pintype "passive+no_connect"))
    )
    (net (code "133") (name "unconnected-(U4-NC-PadN12)") (class "Default")
      (node (ref "U4") (pin "N12") (pinfunction "NC_N12") (pintype "passive+no_connect"))
    )
    (net (code "134") (name "unconnected-(U4-NC-PadN13)") (class "Default")
      (node (ref "U4") (pin "N13") (pinfunction "NC_N13") (pintype "passive+no_connect"))
    )
    (net (code "135") (name "unconnected-(U4-NC-PadN14)") (class "Default")
      (node (ref "U4") (pin "N14") (pinfunction "NC_N14") (pintype "passive+no_connect"))
    )
    (net (code "136") (name "unconnected-(U4-NC-PadP1)") (class "Default")
      (node (ref "U4") (pin "P1") (pinfunction "NC_P1") (pintype "passive+no_connect"))
    )
    (net (code "137") (name "unconnected-(U4-NC-PadP2)") (class "Default")
      (node (ref "U4") (pin "P2") (pinfunction "NC_P2") (pintype "passive+no_connect"))
    )
    (net (code "138") (name "unconnected-(U4-NC-PadP8)") (class "Default")
      (node (ref "U4") (pin "P8") (pinfunction "NC_P8") (pintype "passive+no_connect"))
    )
    (net (code "139") (name "unconnected-(U4-NC-PadP9)") (class "Default")
      (node (ref "U4") (pin "P9") (pinfunction "NC_P9") (pintype "passive+no_connect"))
    )
    (net (code "140") (name "unconnected-(U4-NC-PadP11)") (class "Default")
      (node (ref "U4") (pin "P11") (pinfunction "NC_P11") (pintype "passive+no_connect"))
    )
    (net (code "141") (name "unconnected-(U4-NC-PadP12)") (class "Default")
      (node (ref "U4") (pin "P12") (pinfunction "NC_P12") (pintype "passive+no_connect"))
    )
    (net (code "142") (name "unconnected-(U4-NC-PadP13)") (class "Default")
      (node (ref "U4") (pin "P13") (pinfunction "NC_P13") (pintype "passive+no_connect"))
    )
    (net (code "143") (name "unconnected-(U4-NC-PadP14)") (class "Default")
      (node (ref "U4") (pin "P14") (pinfunction "NC_P14") (pintype "passive+no_connect"))
    )
    (net (code "144") (name "unconnected-(U4-RFU-PadA7)") (class "Default")
      (node (ref "U4") (pin "A7") (pinfunction "RFU_A7") (pintype "passive+no_connect"))
    )
    (net (code "145") (name "unconnected-(U4-RFU-PadE5)") (class "Default")
      (node (ref "U4") (pin "E5") (pinfunction "RFU_E5") (pintype "passive+no_connect"))
    )
    (net (code "146") (name "unconnected-(U4-RFU-PadE8)") (class "Default")
      (node (ref "U4") (pin "E8") (pinfunction "RFU_E8") (pintype "passive+no_connect"))
    )
    (net (code "147") (name "unconnected-(U4-RFU-PadE9)") (class "Default")
      (node (ref "U4") (pin "E9") (pinfunction "RFU_E9") (pintype "passive+no_connect"))
    )
    (net (code "148") (name "unconnected-(U4-RFU-PadE10)") (class "Default")
      (node (ref "U4") (pin "E10") (pinfunction "RFU_E10") (pintype "passive+no_connect"))
    )
    (net (code "149") (name "unconnected-(U4-RFU-PadF10)") (class "Default")
      (node (ref "U4") (pin "F10") (pinfunction "RFU_F10") (pintype "passive+no_connect"))
    )
    (net (code "150") (name "unconnected-(U4-RFU-PadG3)") (class "Default")
      (node (ref "U4") (pin "G3") (pinfunction "RFU_G3") (pintype "passive+no_connect"))
    )
    (net (code "151") (name "unconnected-(U4-RFU-PadG10)") (class "Default")
      (node (ref "U4") (pin "G10") (pinfunction "RFU_G10") (pintype "passive+no_connect"))
    )
    (net (code "152") (name "unconnected-(U4-RFU-PadK6)") (class "Default")
      (node (ref "U4") (pin "K6") (pinfunction "RFU_K6") (pintype "passive+no_connect"))
    )
    (net (code "153") (name "unconnected-(U4-RFU-PadK7)") (class "Default")
      (node (ref "U4") (pin "K7") (pinfunction "RFU_K7") (pintype "passive+no_connect"))
    )
    (net (code "154") (name "unconnected-(U4-RFU-PadK10)") (class "Default")
      (node (ref "U4") (pin "K10") (pinfunction "RFU_K10") (pintype "passive+no_connect"))
    )
    (net (code "155") (name "unconnected-(U4-RFU-PadP7)") (class "Default")
      (node (ref "U4") (pin "P7") (pinfunction "RFU_P7") (pintype "passive+no_connect"))
    )
    (net (code "156") (name "unconnected-(U4-RFU-PadP10)") (class "Default")
      (node (ref "U4") (pin "P10") (pinfunction "RFU_P10") (pintype "passive+no_connect"))
    )
    (net (code "157") (name "unconnected-(U4-VDDF-PadK9)") (class "Default")
      (node (ref "U4") (pin "K9") (pinfunction "VDDF_K9") (pintype "passive+no_connect"))
    )
    (net (code "158") (name "unconnected-(U5-DNU-Pad26)") (class "Default")
      (node (ref "U5") (pin "26") (pinfunction "DNU_26") (pintype "passive+no_connect"))
    )
    (net (code "159") (name "unconnected-(U5-DNU-Pad38)") (class "Default")
      (node (ref "U5") (pin "38") (pinfunction "DNU_38") (pintype "passive+no_connect"))
    )
    (net (code "160") (name "unconnected-(U5-DNU-Pad47)") (class "Default")
      (node (ref "U5") (pin "47") (pinfunction "DNU_47") (pintype "passive+no_connect"))
    )
    (net (code "161") (name "unconnected-(U5-NC-Pad1)") (class "Default")
      (node (ref "U5") (pin "1") (pinfunction "NC_1") (pintype "passive+no_connect"))
    )
    (net (code "162") (name "unconnected-(U5-NC-Pad2)") (class "Default")
      (node (ref "U5") (pin "2") (pinfunction "NC_2") (pintype "passive+no_connect"))
    )
    (net (code "163") (name "unconnected-(U5-NC-Pad3)") (class "Default")
      (node (ref "U5") (pin "3") (pinfunction "NC_3") (pintype "passive+no_connect"))
    )
    (net (code "164") (name "unconnected-(U5-NC-Pad4)") (class "Default")
      (node (ref "U5") (pin "4") (pinfunction "NC_4") (pintype "passive+no_connect"))
    )
    (net (code "165") (name "unconnected-(U5-NC-Pad5)") (class "Default")
      (node (ref "U5") (pin "5") (pinfunction "NC_5") (pintype "passive+no_connect"))
    )
    (net (code "166") (name "unconnected-(U5-NC-Pad11)") (class "Default")
      (node (ref "U5") (pin "11") (pinfunction "NC_11") (pintype "passive+no_connect"))
    )
    (net (code "167") (name "unconnected-(U5-NC-Pad14)") (class "Default")
      (node (ref "U5") (pin "14") (pinfunction "NC_14") (pintype "passive+no_connect"))
    )
    (net (code "168") (name "unconnected-(U5-NC-Pad15)") (class "Default")
      (node (ref "U5") (pin "15") (pinfunction "NC_15") (pintype "passive+no_connect"))
    )
    (net (code "169") (name "unconnected-(U5-NC-Pad20)") (class "Default")
      (node (ref "U5") (pin "20") (pinfunction "NC_20") (pintype "passive+no_connect"))
    )
    (net (code "170") (name "unconnected-(U5-NC-Pad21)") (class "Default")
      (node (ref "U5") (pin "21") (pinfunction "NC_21") (pintype "passive+no_connect"))
    )
    (net (code "171") (name "unconnected-(U5-NC-Pad22)") (class "Default")
      (node (ref "U5") (pin "22") (pinfunction "NC_22") (pintype "passive+no_connect"))
    )
    (net (code "172") (name "unconnected-(U5-NC-Pad23)") (class "Default")
      (node (ref "U5") (pin "23") (pinfunction "NC_23") (pintype "passive+no_connect"))
    )
    (net (code "173") (name "unconnected-(U5-NC-Pad24)") (class "Default")
      (node (ref "U5") (pin "24") (pinfunction "NC_24") (pintype "passive+no_connect"))
    )
    (net (code "174") (name "unconnected-(U5-NC-Pad27)") (class "Default")
      (node (ref "U5") (pin "27") (pinfunction "NC_27") (pintype "passive+no_connect"))
    )
    (net (code "175") (name "unconnected-(U5-NC-Pad33)") (class "Default")
      (node (ref "U5") (pin "33") (pinfunction "NC_33") (pintype "passive+no_connect"))
    )
    (net (code "176") (name "unconnected-(U5-NC-Pad35)") (class "Default")
      (node (ref "U5") (pin "35") (pinfunction "NC_35") (pintype "passive+no_connect"))
    )
    (net (code "177") (name "unconnected-(U5-NC-Pad40)") (class "Default")
      (node (ref "U5") (pin "40") (pinfunction "NC_40") (pintype "passive+no_connect"))
    )
    (net (code "178") (name "unconnected-(U5-NC-Pad45)") (class "Default")
      (node (ref "U5") (pin "45") (pinfunction "NC_45") (pintype "passive+no_connect"))
    )
    (net (code "179") (name "unconnected-(U5-NC-Pad46)") (class "Default")
      (node (ref "U5") (pin "46") (pinfunction "NC_46") (pintype "passive+no_connect"))
    )
  )
)
